# UserInputs.net
KiCad netlist of a schematic drawn in Altium Designer
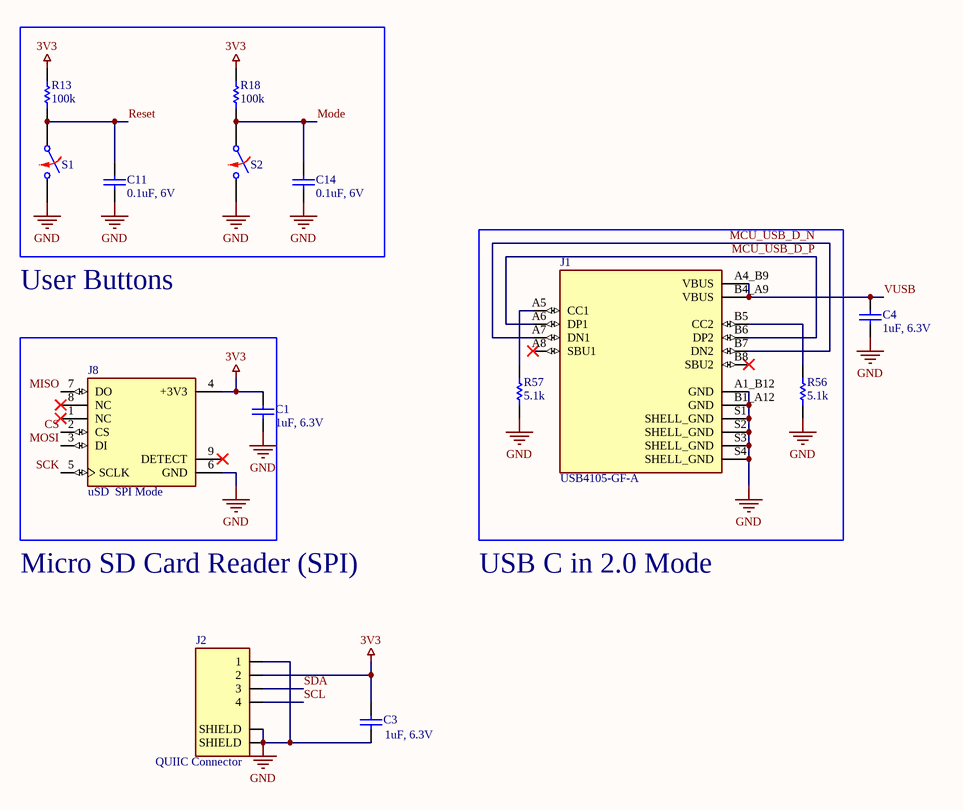
[diagram p0: UserInputs.SchDoc]

(export (version "E")
  (design (tool "Eeschema 10.0.6"))
  (components
    (comp (ref "C1")
      (value "1uF, 6.3V")
      (footprint "ANTC1608X90N")
      (description "Capacitor")
      (libsource (lib "Simulation Generic Components") (part "Capacitor"))
    )
    (comp (ref "C3")
      (value "1uF, 6.3V")
      (footprint "ANTC1608X90N")
      (description "Capacitor")
      (libsource (lib "Simulation Generic Components") (part "Capacitor"))
    )
    (comp (ref "C4")
      (value "1uF, 6.3V")
      (footprint "ANTC1608X90N")
      (description "Capacitor")
      (libsource (lib "Simulation Generic Components") (part "Capacitor"))
    )
    (comp (ref "C11")
      (value "0.1uF, 6V")
      (footprint "ANTC1608X90N")
      (description "Capacitor")
      (libsource (lib "Simulation Generic Components") (part "Capacitor"))
    )
    (comp (ref "C14")
      (value "0.1uF, 6V")
      (footprint "ANTC1608X90N")
      (description "Capacitor")
      (libsource (lib "Simulation Generic Components") (part "Capacitor"))
    )
    (comp (ref "J1")
      (value "USB4105-GF-A")
      (footprint "GCT_USB4105-GF-A")
      (libsource (lib "USB4105-GF-A") (part "USB4105-GF-A"))
    )
    (comp (ref "J2")
      (value "QUIIC Connector")
      (footprint "JST_SM04B-SRSS-TB(LF)(SN)")
      (description "SH Series 1.0 mm Pitch 2 Position Single Row Side Entry Shrouded Header")
      (fields (field (name "MP") "SM04B-SRSS-TB(LF)(SN)"))
      (libsource (lib "SM04B-SRSS-TB(LF)(SN)") (part "SM04B-SRSS-TB(LF)(SN)"))
    )
    (comp (ref "J8")
      (value "uSD  SPI Mode")
      (footprint "GCT_MEM2051-00-195-00-A")
      (fields (field (name "MF") "Global Connector Technology") (field (name "MP") "MEM2051-00-195-00-A"))
      (libsource (lib "MEM2051-00-195-00-A") (part "MEM2051-00-195-00-A"))
    )
    (comp (ref "R13")
      (value "100k")
      (footprint "0603 Resistor")
      (description "Resistor")
      (libsource (lib "Simulation Generic Components") (part "Resistor"))
    )
    (comp (ref "R18")
      (value "100k")
      (footprint "0603 Resistor")
      (description "Resistor")
      (libsource (lib "Simulation Generic Components") (part "Resistor"))
    )
    (comp (ref "R56")
      (value "5.1k")
      (footprint "0603 Resistor")
      (description "Resistor")
      (libsource (lib "Simulation Generic Components") (part "Resistor"))
    )
    (comp (ref "R57")
      (value "5.1k")
      (footprint "0603 Resistor")
      (description "Resistor")
      (libsource (lib "Simulation Generic Components") (part "Resistor"))
    )
    (comp (ref "S1")
      (value "Switch Normally Opened")
      (footprint "TL3313AF250QG")
      (libsource (lib "Simulation Generic Components") (part "SW NO"))
    )
    (comp (ref "S2")
      (value "Switch Normally Opened")
      (footprint "TL3313AF250QG")
      (libsource (lib "Simulation Generic Components") (part "SW NO"))
    )
  )
  (nets
    (net (code "1") (name "/CS") (class "Default")
      (node (ref "J8") (pin "2") (pinfunction "CS_2") (pintype "bidirectional"))
    )
    (net (code "2") (name "/MCU_USB_D_N") (class "Default")
      (node (ref "J1") (pin "A7") (pinfunction "DN1_A7") (pintype "bidirectional"))
      (node (ref "J1") (pin "B7") (pinfunction "DN2_B7") (pintype "bidirectional"))
    )
    (net (code "3") (name "/MCU_USB_D_P") (class "Default")
      (node (ref "J1") (pin "A6") (pinfunction "DP1_A6") (pintype "bidirectional"))
      (node (ref "J1") (pin "B6") (pinfunction "DP2_B6") (pintype "bidirectional"))
    )
    (net (code "4") (name "/MISO") (class "Default")
      (node (ref "J8") (pin "7") (pinfunction "DO_7") (pintype "bidirectional"))
    )
    (net (code "5") (name "/MOSI") (class "Default")
      (node (ref "J8") (pin "3") (pinfunction "DI_3") (pintype "bidirectional"))
    )
    (net (code "6") (name "/Mode") (class "Default")
      (node (ref "C14") (pin "2") (pinfunction "2_2") (pintype "passive"))
      (node (ref "R18") (pin "1") (pinfunction "1_1") (pintype "passive"))
      (node (ref "S2") (pin "1") (pinfunction "1_1") (pintype "passive"))
    )
    (net (code "7") (name "/Reset") (class "Default")
      (node (ref "C11") (pin "2") (pinfunction "2_2") (pintype "passive"))
      (node (ref "R13") (pin "1") (pinfunction "1_1") (pintype "passive"))
      (node (ref "S1") (pin "1") (pinfunction "1_1") (pintype "passive"))
    )
    (net (code "8") (name "/SCK") (class "Default")
      (node (ref "J8") (pin "5") (pinfunction "SCLK_5") (pintype "bidirectional"))
    )
    (net (code "9") (name "/SCL") (class "Default")
      (node (ref "J2") (pin "4") (pinfunction "4_4") (pintype "passive"))
    )
    (net (code "10") (name "/SDA") (class "Default")
      (node (ref "J2") (pin "3") (pinfunction "3_3") (pintype "passive"))
    )
    (net (code "11") (name "/VUSB") (class "Default")
      (node (ref "C4") (pin "2") (pinfunction "2_2") (pintype "passive"))
      (node (ref "J1") (pin "A4_B9") (pinfunction "VBUS_A4_B9") (pintype "power_in"))
      (node (ref "J1") (pin "B4_A9") (pinfunction "VBUS_B4_A9") (pintype "power_in"))
    )
    (net (code "12") (name "3V3") (class "Default")
      (node (ref "C1") (pin "2") (pinfunction "2_2") (pintype "passive"))
      (node (ref "C3") (pin "2") (pinfunction "2_2") (pintype "passive"))
      (node (ref "J2") (pin "2") (pinfunction "2_2") (pintype "passive"))
      (node (ref "J8") (pin "4") (pinfunction "+3V3_4") (pintype "power_in"))
      (node (ref "R13") (pin "2") (pinfunction "2_2") (pintype "passive"))
      (node (ref "R18") (pin "2") (pinfunction "2_2") (pintype "passive"))
    )
    (net (code "13") (name "GND") (class "Default")
      (node (ref "C1") (pin "1") (pinfunction "1_1") (pintype "passive"))
      (node (ref "C11") (pin "1") (pinfunction "1_1") (pintype "passive"))
      (node (ref "C14") (pin "1") (pinfunction "1_1") (pintype "passive"))
      (node (ref "C3") (pin "1") (pinfunction "1_1") (pintype "passive"))
      (node (ref "C4") (pin "1") (pinfunction "1_1") (pintype "passive"))
      (node (ref "J1") (pin "A1_B12") (pinfunction "GND_A1_B12") (pintype "power_in"))
      (node (ref "J1") (pin "B1_A12") (pinfunction "GND_B1_A12") (pintype "power_in"))
      (node (ref "J1") (pin "S1") (pinfunction "SHELL_GND_S1") (pintype "power_in"))
      (node (ref "J1") (pin "S2") (pinfunction "SHELL_GND_S2") (pintype "power_in"))
      (node (ref "J1") (pin "S3") (pinfunction "SHELL_GND_S3") (pintype "power_in"))
      (node (ref "J1") (pin "S4") (pinfunction "SHELL_GND_S4") (pintype "power_in"))
      (node (ref "J2") (pin "1") (pinfunction "1_1") (pintype "passive"))
      (node (ref "J2") (pin "S1") (pinfunction "SHIELD_S1") (pintype "passive"))
      (node (ref "J2") (pin "S2") (pinfunction "SHIELD_S2") (pintype "passive"))
      (node (ref "J8") (pin "6") (pinfunction "GND_6") (pintype "power_in"))
      (node (ref "R56") (pin "1") (pinfunction "1_1") (pintype "passive"))
      (node (ref "R57") (pin "1") (pinfunction "1_1") (pintype "passive"))
      (node (ref "S1") (pin "2") (pinfunction "2_2") (pintype "passive"))
      (node (ref "S2") (pin "2") (pinfunction "2_2") (pintype "passive"))
    )
    (net (code "14") (name "Net-(J1-CC1)") (class "Default")
      (node (ref "J1") (pin "A5") (pinfunction "CC1_A5") (pintype "bidirectional"))
      (node (ref "R57") (pin "2") (pinfunction "2_2") (pintype "passive"))
    )
    (net (code "15") (name "Net-(J1-CC2)") (class "Default")
      (node (ref "J1") (pin "B5") (pinfunction "CC2_B5") (pintype "bidirectional"))
      (node (ref "R56") (pin "2") (pinfunction "2_2") (pintype "passive"))
    )
    (net (code "16") (name "unconnected-(J1-SBU1-PadA8)") (class "Default")
      (node (ref "J1") (pin "A8") (pinfunction "SBU1_A8") (pintype "bidirectional+no_connect"))
    )
    (net (code "17") (name "unconnected-(J1-SBU2-PadB8)") (class "Default")
      (node (ref "J1") (pin "B8") (pinfunction "SBU2_B8") (pintype "bidirectional+no_connect"))
    )
    (net (code "18") (name "unconnected-(J8-DETECT-Pad9)") (class "Default")
      (node (ref "J8") (pin "9") (pinfunction "DETECT_9") (pintype "passive+no_connect"))
    )
    (net (code "19") (name "unconnected-(J8-NC-Pad1)") (class "Default")
      (node (ref "J8") (pin "1") (pinfunction "NC_1") (pintype "tri_state+no_connect"))
    )
    (net (code "20") (name "unconnected-(J8-NC-Pad8)") (class "Default")
      (node (ref "J8") (pin "8") (pinfunction "NC_8") (pintype "tri_state+no_connect"))
    )
  )
)
